# Main.net
KiCad netlist of a schematic drawn in EAGLE
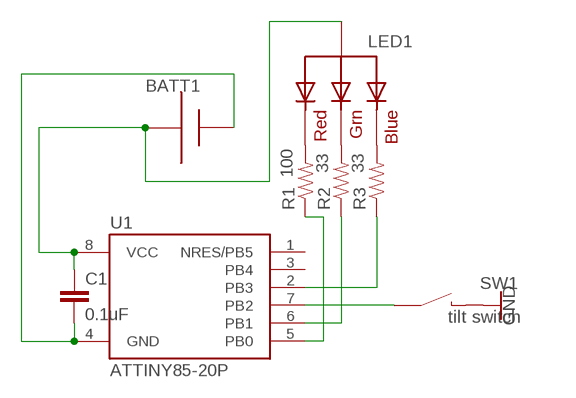
[diagram p0: schematic, sheet 1]

(export (version "E")
  (design (tool "Eeschema 10.0.6"))
  (components
    (comp (ref "BATT1")
      (value "AAA")
      (footprint "eagle-import:12BH412")
      (libsource (lib "eagle-import") (part "AAA"))
    )
    (comp (ref "C1")
      (value "0.1uF")
      (footprint "eagle-import:0603")
      (libsource (lib "eagle-import") (part "0.1UF-0603-25V-(+80/-20%)"))
    )
    (comp (ref "LED1")
      (value "RGBLED_CA-5MM")
      (footprint "eagle-import:LED5MMRGB")
      (libsource (lib "eagle-import") (part "RGBLED_CA-5MM"))
    )
    (comp (ref "R1")
      (value "100")
      (footprint "eagle-import:0603")
      (libsource (lib "eagle-import") (part "33OHM-0603-1/10W-1%"))
    )
    (comp (ref "R2")
      (value "33")
      (footprint "eagle-import:0603")
      (libsource (lib "eagle-import") (part "33OHM-0603-1/10W-1%"))
    )
    (comp (ref "R3")
      (value "33")
      (footprint "eagle-import:0603")
      (libsource (lib "eagle-import") (part "33OHM-0603-1/10W-1%"))
    )
    (comp (ref "SW1")
      (value "46202LRX")
      (footprint "eagle-import:46202LRX")
      (fields (field (name "TYPE") "tilt switch"))
      (libsource (lib "eagle-import") (part "46202LRX"))
    )
    (comp (ref "U1")
      (value "ATTINY85-20P")
      (footprint "eagle-import:PDIP08_300MIL")
      (libsource (lib "eagle-import") (part "ATTINY85P-20"))
    )
  )
  (nets
    (net (code "1") (name "GND") (class "Default")
      (node (ref "SW1") (pin "P$2") (pinfunction "B_P$2") (pintype "passive"))
    )
    (net (code "2") (name "Net-(LED1-BLUE)") (class "Default")
      (node (ref "LED1") (pin "4") (pinfunction "BLUE_4") (pintype "bidirectional"))
      (node (ref "R3") (pin "2") (pinfunction "2_2") (pintype "passive"))
    )
    (net (code "3") (name "Net-(LED1-GREEN)") (class "Default")
      (node (ref "LED1") (pin "3") (pinfunction "GREEN_3") (pintype "bidirectional"))
      (node (ref "R2") (pin "2") (pinfunction "2_2") (pintype "passive"))
    )
    (net (code "4") (name "Net-(LED1-RED)") (class "Default")
      (node (ref "LED1") (pin "1") (pinfunction "RED_1") (pintype "bidirectional"))
      (node (ref "R1") (pin "2") (pinfunction "2_2") (pintype "passive"))
    )
    (net (code "5") (name "Net-(LED1-VCC)") (class "Default")
      (node (ref "BATT1") (pin "-") (pinfunction "-_-") (pintype "bidirectional"))
      (node (ref "C1") (pin "1") (pinfunction "1_1") (pintype "passive"))
      (node (ref "LED1") (pin "2") (pinfunction "VCC_2") (pintype "bidirectional"))
      (node (ref "U1") (pin "8") (pinfunction "VCC_8") (pintype "power_in"))
    )
    (net (code "6") (name "Net-(SW1-A1)") (class "Default")
      (node (ref "SW1") (pin "P$1") (pinfunction "A1_P$1") (pintype "passive"))
      (node (ref "U1") (pin "7") (pinfunction "PB2_7") (pintype "bidirectional"))
    )
    (net (code "7") (name "Net-(U1-GND)") (class "Default")
      (node (ref "BATT1") (pin "+") (pinfunction "+_+") (pintype "bidirectional"))
      (node (ref "C1") (pin "2") (pinfunction "2_2") (pintype "passive"))
      (node (ref "U1") (pin "4") (pinfunction "GND_4") (pintype "power_in"))
    )
    (net (code "8") (name "Net-(U1-PB0)") (class "Default")
      (node (ref "R1") (pin "1") (pinfunction "1_1") (pintype "passive"))
      (node (ref "U1") (pin "5") (pinfunction "PB0_5") (pintype "bidirectional"))
    )
    (net (code "9") (name "Net-(U1-PB1)") (class "Default")
      (node (ref "R2") (pin "1") (pinfunction "1_1") (pintype "passive"))
      (node (ref "U1") (pin "6") (pinfunction "PB1_6") (pintype "bidirectional"))
    )
    (net (code "10") (name "Net-(U1-PB3)") (class "Default")
      (node (ref "R3") (pin "1") (pinfunction "1_1") (pintype "passive"))
      (node (ref "U1") (pin "2") (pinfunction "PB3_2") (pintype "bidirectional"))
    )
    (net (code "11") (name "unconnected-(U1-NRES{slash}PB5-Pad1)") (class "Default")
      (node (ref "U1") (pin "1") (pinfunction "NRES/PB5_1") (pintype "bidirectional"))
    )
    (net (code "12") (name "unconnected-(U1-PB4-Pad3)") (class "Default")
      (node (ref "U1") (pin "3") (pinfunction "PB4_3") (pintype "bidirectional"))
    )
  )
)
